# DAC.net
KiCad netlist of a schematic drawn in Altium Designer
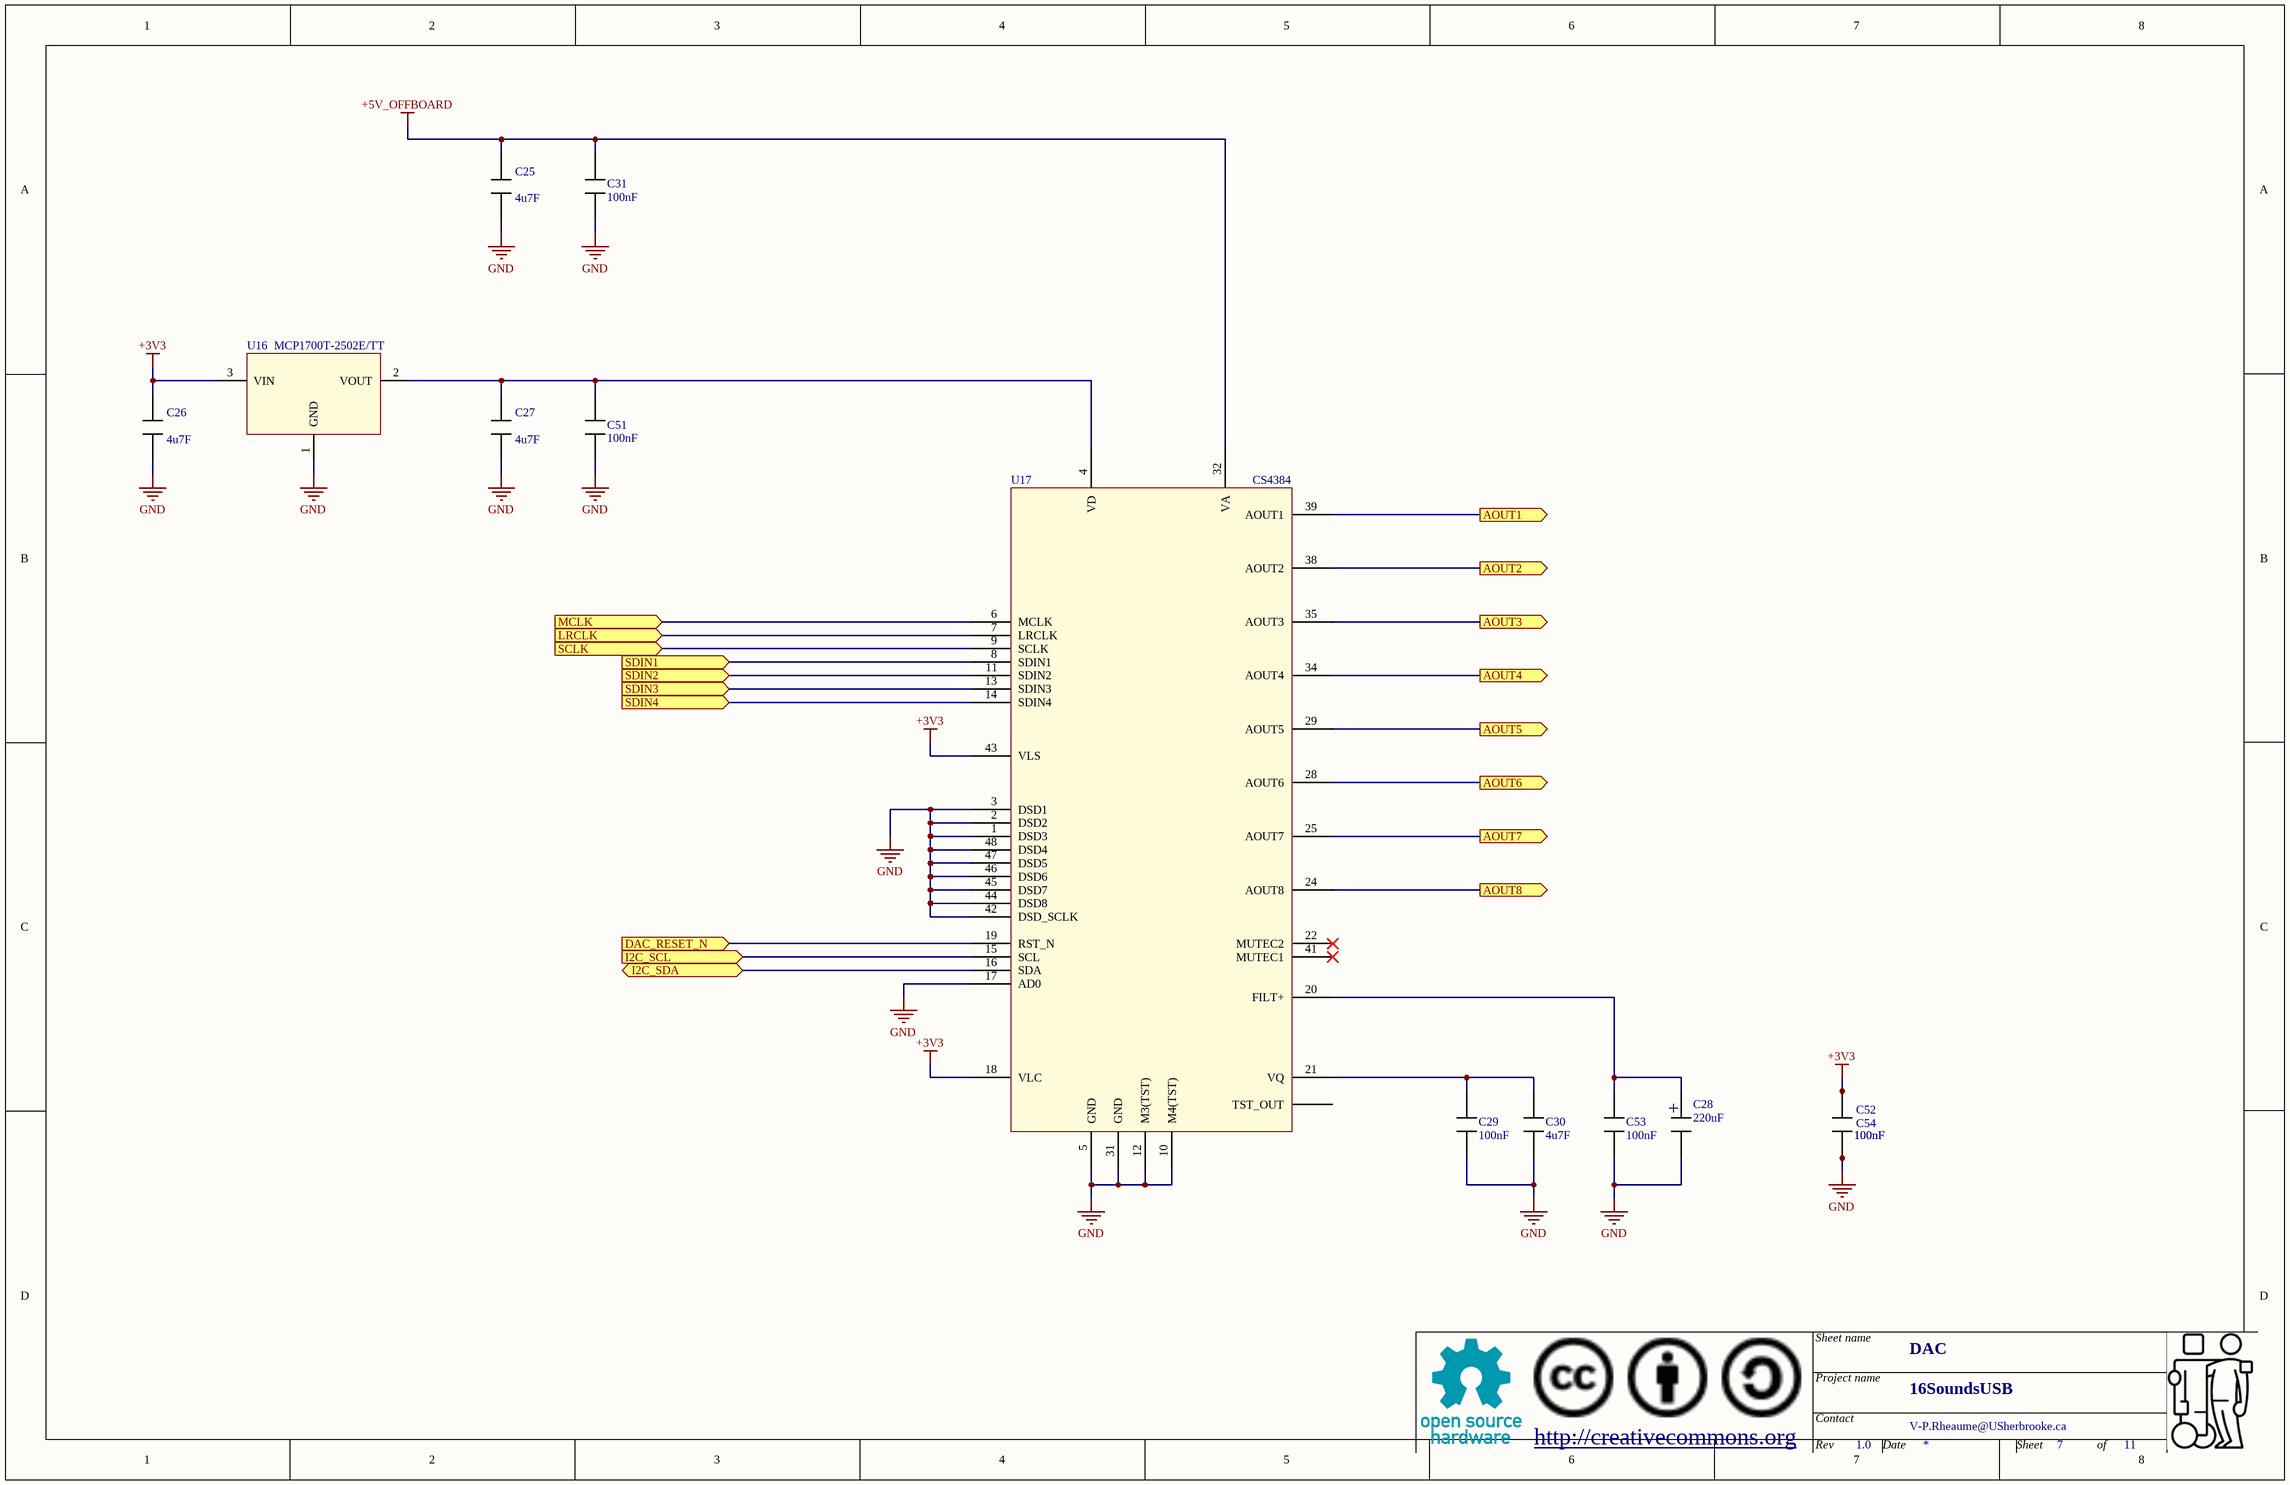
[diagram p0: DAC.SchDoc]

(export (version "E")
  (design (tool "Eeschema 10.0.6"))
  (components
    (comp (ref "C25")
      (value "4u7F")
      (footprint "0805")
      (description "Capacitor")
      (libsource (lib "INTER_2014") (part "Capacitor"))
    )
    (comp (ref "C26")
      (value "4u7F")
      (footprint "0805")
      (description "Capacitor")
      (libsource (lib "INTER_2014") (part "Capacitor"))
    )
    (comp (ref "C27")
      (value "4u7F")
      (footprint "0805")
      (description "Capacitor")
      (libsource (lib "INTER_2014") (part "Capacitor"))
    )
    (comp (ref "C28")
      (value "220uF")
      (footprint "CAP_RAD_SMD_DIA315")
      (description "Capacitor")
      (fields (field (name "Comment") "Capacitor_Polarized"))
      (libsource (lib "INTER_2014") (part "Capacitor_Polarized"))
    )
    (comp (ref "C29")
      (value "100nF")
      (footprint "0603")
      (description "Capacitor")
      (libsource (lib "INTER_2014") (part "Capacitor"))
    )
    (comp (ref "C30")
      (value "4u7F")
      (footprint "0805")
      (description "Capacitor")
      (libsource (lib "INTER_2014") (part "Capacitor"))
    )
    (comp (ref "C31")
      (value "100nF")
      (footprint "0603")
      (description "Capacitor")
      (libsource (lib "INTER_2014") (part "Capacitor"))
    )
    (comp (ref "C51")
      (value "100nF")
      (footprint "0603")
      (description "Capacitor")
      (libsource (lib "INTER_2014") (part "Capacitor"))
    )
    (comp (ref "C52")
      (value "100nF")
      (footprint "0603")
      (description "Capacitor")
      (libsource (lib "INTER_2014") (part "Capacitor"))
    )
    (comp (ref "C53")
      (value "100nF")
      (footprint "0603")
      (description "Capacitor")
      (libsource (lib "INTER_2014") (part "Capacitor"))
    )
    (comp (ref "C54")
      (value "100nF")
      (footprint "0603")
      (description "Capacitor")
      (libsource (lib "INTER_2014") (part "Capacitor"))
    )
    (comp (ref "U16")
      (value "MCP1700")
      (footprint "SOT23_132")
      (description "Linear voltage regulator")
      (fields (field (name "MFG") "Microchip") (field (name "MFG_PN") "MCP1700T-2502E/TT"))
      (libsource (lib "INTER_2014") (part "MCP1700"))
    )
    (comp (ref "U17")
      (value "CS4384")
      (footprint "LQFP_48L_CIRRUS")
      (description "DAC, 24-bit, 8 chan, 192kHz, PCM, TDM, DSD, LQFP48")
      (fields (field (name "MFG") "Cirrus"))
      (libsource (lib "INTER_2014") (part "CS4384"))
    )
  )
  (nets
    (net (code "1") (name "+3V3") (class "Default")
      (node (ref "C26") (pin "1") (pintype "passive"))
      (node (ref "C52") (pin "1") (pintype "passive"))
      (node (ref "C54") (pin "1") (pintype "passive"))
      (node (ref "U16") (pin "3") (pinfunction "VIN_3") (pintype "passive"))
      (node (ref "U17") (pin "18") (pinfunction "VLC_18") (pintype "passive"))
      (node (ref "U17") (pin "43") (pinfunction "VLS_43") (pintype "passive"))
    )
    (net (code "2") (name "+5V_OFFBOARD") (class "Default")
      (node (ref "C25") (pin "1") (pintype "passive"))
      (node (ref "C31") (pin "1") (pintype "passive"))
      (node (ref "U17") (pin "32") (pinfunction "VA_32") (pintype "passive"))
    )
    (net (code "3") (name "/AOUT1") (class "Default")
      (node (ref "U17") (pin "39") (pinfunction "AOUT1_39") (pintype "passive"))
    )
    (net (code "4") (name "/AOUT2") (class "Default")
      (node (ref "U17") (pin "38") (pinfunction "AOUT2_38") (pintype "passive"))
    )
    (net (code "5") (name "/AOUT3") (class "Default")
      (node (ref "U17") (pin "35") (pinfunction "AOUT3_35") (pintype "passive"))
    )
    (net (code "6") (name "/AOUT4") (class "Default")
      (node (ref "U17") (pin "34") (pinfunction "AOUT4_34") (pintype "passive"))
    )
    (net (code "7") (name "/AOUT5") (class "Default")
      (node (ref "U17") (pin "29") (pinfunction "AOUT5_29") (pintype "passive"))
    )
    (net (code "8") (name "/AOUT6") (class "Default")
      (node (ref "U17") (pin "28") (pinfunction "AOUT6_28") (pintype "passive"))
    )
    (net (code "9") (name "/AOUT7") (class "Default")
      (node (ref "U17") (pin "25") (pinfunction "AOUT7_25") (pintype "passive"))
    )
    (net (code "10") (name "/AOUT8") (class "Default")
      (node (ref "U17") (pin "24") (pinfunction "AOUT8_24") (pintype "passive"))
    )
    (net (code "11") (name "/DAC_RESET_N") (class "Default")
      (node (ref "U17") (pin "19") (pinfunction "RST_N_19") (pintype "passive"))
    )
    (net (code "12") (name "/I2C_SCL") (class "Default")
      (node (ref "U17") (pin "15") (pinfunction "SCL_15") (pintype "passive"))
    )
    (net (code "13") (name "/I2C_SDA") (class "Default")
      (node (ref "U17") (pin "16") (pinfunction "SDA_16") (pintype "passive"))
    )
    (net (code "14") (name "/LRCLK") (class "Default")
      (node (ref "U17") (pin "7") (pinfunction "LRCLK_7") (pintype "passive"))
    )
    (net (code "15") (name "/MCLK") (class "Default")
      (node (ref "U17") (pin "6") (pinfunction "MCLK_6") (pintype "passive"))
    )
    (net (code "16") (name "/SCLK") (class "Default")
      (node (ref "U17") (pin "9") (pinfunction "SCLK_9") (pintype "passive"))
    )
    (net (code "17") (name "/SDIN1") (class "Default")
      (node (ref "U17") (pin "8") (pinfunction "SDIN1_8") (pintype "passive"))
    )
    (net (code "18") (name "/SDIN2") (class "Default")
      (node (ref "U17") (pin "11") (pinfunction "SDIN2_11") (pintype "passive"))
    )
    (net (code "19") (name "/SDIN3") (class "Default")
      (node (ref "U17") (pin "13") (pinfunction "SDIN3_13") (pintype "passive"))
    )
    (net (code "20") (name "/SDIN4") (class "Default")
      (node (ref "U17") (pin "14") (pinfunction "SDIN4_14") (pintype "passive"))
    )
    (net (code "21") (name "GND") (class "Default")
      (node (ref "C25") (pin "2") (pintype "passive"))
      (node (ref "C26") (pin "2") (pintype "passive"))
      (node (ref "C27") (pin "2") (pintype "passive"))
      (node (ref "C28") (pin "-") (pintype "passive"))
      (node (ref "C29") (pin "2") (pintype "passive"))
      (node (ref "C30") (pin "2") (pintype "passive"))
      (node (ref "C31") (pin "2") (pintype "passive"))
      (node (ref "C51") (pin "2") (pintype "passive"))
      (node (ref "C52") (pin "2") (pintype "passive"))
      (node (ref "C53") (pin "2") (pintype "passive"))
      (node (ref "C54") (pin "2") (pintype "passive"))
      (node (ref "U16") (pin "1") (pinfunction "GND_1") (pintype "passive"))
      (node (ref "U17") (pin "1") (pinfunction "DSD3_1") (pintype "passive"))
      (node (ref "U17") (pin "10") (pinfunction "M4(TST)_10") (pintype "passive"))
      (node (ref "U17") (pin "12") (pinfunction "M3(TST)_12") (pintype "passive"))
      (node (ref "U17") (pin "17") (pinfunction "AD0_17") (pintype "passive"))
      (node (ref "U17") (pin "2") (pinfunction "DSD2_2") (pintype "passive"))
      (node (ref "U17") (pin "3") (pinfunction "DSD1_3") (pintype "passive"))
      (node (ref "U17") (pin "31") (pinfunction "GND_31") (pintype "passive"))
      (node (ref "U17") (pin "42") (pinfunction "DSD_SCLK_42") (pintype "passive"))
      (node (ref "U17") (pin "44") (pinfunction "DSD8_44") (pintype "passive"))
      (node (ref "U17") (pin "45") (pinfunction "DSD7_45") (pintype "passive"))
      (node (ref "U17") (pin "46") (pinfunction "DSD6_46") (pintype "passive"))
      (node (ref "U17") (pin "47") (pinfunction "DSD5_47") (pintype "passive"))
      (node (ref "U17") (pin "48") (pinfunction "DSD4_48") (pintype "passive"))
      (node (ref "U17") (pin "5") (pinfunction "GND_5") (pintype "passive"))
    )
    (net (code "22") (name "Net-(U16-VOUT)") (class "Default")
      (node (ref "C27") (pin "1") (pintype "passive"))
      (node (ref "C51") (pin "1") (pintype "passive"))
      (node (ref "U16") (pin "2") (pinfunction "VOUT_2") (pintype "passive"))
      (node (ref "U17") (pin "4") (pinfunction "VD_4") (pintype "passive"))
    )
    (net (code "23") (name "Net-(U17-FILT+)") (class "Default")
      (node (ref "C28") (pin "+") (pintype "passive"))
      (node (ref "C53") (pin "1") (pintype "passive"))
      (node (ref "U17") (pin "20") (pinfunction "FILT+_20") (pintype "passive"))
    )
    (net (code "24") (name "Net-(U17-VQ)") (class "Default")
      (node (ref "C29") (pin "1") (pintype "passive"))
      (node (ref "C30") (pin "1") (pintype "passive"))
      (node (ref "U17") (pin "21") (pinfunction "VQ_21") (pintype "passive"))
    )
    (net (code "25") (name "unconnected-(U17-MUTEC1-Pad41)") (class "Default")
      (node (ref "U17") (pin "41") (pinfunction "MUTEC1_41") (pintype "passive+no_connect"))
    )
    (net (code "26") (name "unconnected-(U17-MUTEC2-Pad22)") (class "Default")
      (node (ref "U17") (pin "22") (pinfunction "MUTEC2_22") (pintype "passive+no_connect"))
    )
    (net (code "27") (name "unconnected-(U17-TST_OUT-Pad23)") (class "Default")
      (node (ref "U17") (pin "23") (pinfunction "TST_OUT_23") (pintype "passive"))
    )
    (net (code "28") (name "unconnected-(U17-TST_OUT-Pad26)") (class "Default")
      (node (ref "U17") (pin "26") (pinfunction "TST_OUT_26") (pintype "passive"))
    )
    (net (code "29") (name "unconnected-(U17-TST_OUT-Pad27)") (class "Default")
      (node (ref "U17") (pin "27") (pinfunction "TST_OUT_27") (pintype "passive"))
    )
    (net (code "30") (name "unconnected-(U17-TST_OUT-Pad30)") (class "Default")
      (node (ref "U17") (pin "30") (pinfunction "TST_OUT_30") (pintype "passive"))
    )
    (net (code "31") (name "unconnected-(U17-TST_OUT-Pad33)") (class "Default")
      (node (ref "U17") (pin "33") (pinfunction "TST_OUT_33") (pintype "passive"))
    )
    (net (code "32") (name "unconnected-(U17-TST_OUT-Pad36)") (class "Default")
      (node (ref "U17") (pin "36") (pinfunction "TST_OUT_36") (pintype "passive"))
    )
    (net (code "33") (name "unconnected-(U17-TST_OUT-Pad37)") (class "Default")
      (node (ref "U17") (pin "37") (pinfunction "TST_OUT_37") (pintype "passive"))
    )
    (net (code "34") (name "unconnected-(U17-TST_OUT-Pad40)") (class "Default")
      (node (ref "U17") (pin "40") (pinfunction "TST_OUT_40") (pintype "passive"))
    )
  )
)
